# MOTOR.net
KiCad netlist of a schematic drawn in Altium Designer
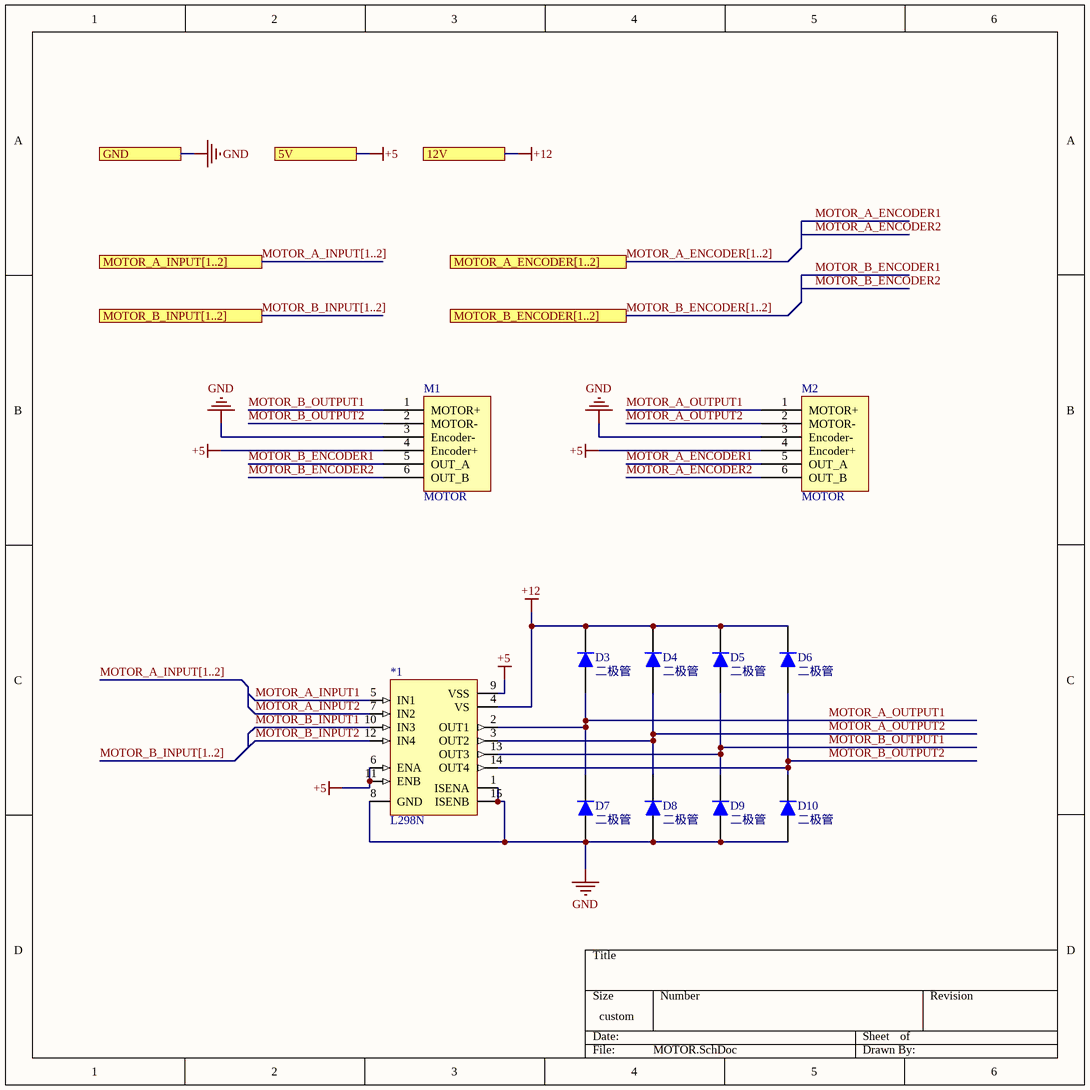
[diagram p0: MOTOR.SchDoc]

(export (version "E")
  (design (tool "Eeschema 10.0.6"))
  (components
    (comp (ref "*1") (value "L298N") (footprint "L298N-DIP") (libsource (lib "Schlib1") (part "L298N")))
    (comp (ref "D3") (value "二极管") (footprint "SOD-323") (libsource (lib "Schlib1") (part "二极管 SOD323")))
    (comp (ref "D4") (value "二极管") (footprint "SOD-323") (libsource (lib "Schlib1") (part "二极管 SOD323")))
    (comp (ref "D5") (value "二极管") (footprint "SOD-323") (libsource (lib "Schlib1") (part "二极管 SOD323")))
    (comp (ref "D6") (value "二极管") (footprint "SOD-323") (libsource (lib "Schlib1") (part "二极管 SOD323")))
    (comp (ref "D7") (value "二极管") (footprint "SOD-323") (libsource (lib "Schlib1") (part "二极管 SOD323")))
    (comp (ref "D8") (value "二极管") (footprint "SOD-323") (libsource (lib "Schlib1") (part "二极管 SOD323")))
    (comp (ref "D9") (value "二极管") (footprint "SOD-323") (libsource (lib "Schlib1") (part "二极管 SOD323")))
    (comp (ref "D10") (value "二极管") (footprint "SOD-323") (libsource (lib "Schlib1") (part "二极管 SOD323")))
    (comp (ref "M1")
      (value "MOTOR")
      (footprint "MOTOR_PORT ClearVer")
      (libsource (lib "Schlib1") (part "MOTOR_Port"))
    )
    (comp (ref "M2")
      (value "MOTOR")
      (footprint "MOTOR_PORT ClearVer")
      (libsource (lib "Schlib1") (part "MOTOR_Port"))
    )
  )
  (nets
    (net (code "1") (name "+5") (class "Default")
      (node (ref "*1") (pin "11") (pinfunction "ENB_11") (pintype "input"))
      (node (ref "*1") (pin "6") (pinfunction "ENA_6") (pintype "input"))
      (node (ref "*1") (pin "9") (pinfunction "VSS_9") (pintype "passive"))
      (node (ref "M1") (pin "4") (pinfunction "Encoder+_4") (pintype "passive"))
      (node (ref "M2") (pin "4") (pinfunction "Encoder+_4") (pintype "passive"))
    )
    (net (code "2") (name "+12") (class "Default")
      (node (ref "*1") (pin "4") (pinfunction "VS_4") (pintype "passive"))
      (node (ref "D3") (pin "1") (pinfunction "1_1") (pintype "passive"))
      (node (ref "D4") (pin "1") (pinfunction "1_1") (pintype "passive"))
      (node (ref "D5") (pin "1") (pinfunction "1_1") (pintype "passive"))
      (node (ref "D6") (pin "1") (pinfunction "1_1") (pintype "passive"))
    )
    (net (code "3") (name "/MOTOR_A_ENCODER1") (class "Default")
      (node (ref "M2") (pin "5") (pinfunction "OUT_A_5") (pintype "passive"))
    )
    (net (code "4") (name "/MOTOR_A_ENCODER2") (class "Default")
      (node (ref "M2") (pin "6") (pinfunction "OUT_B_6") (pintype "passive"))
    )
    (net (code "6") (name "/MOTOR_A_INPUT1") (class "Default")
      (node (ref "*1") (pin "5") (pinfunction "IN1_5") (pintype "input"))
    )
    (net (code "7") (name "/MOTOR_A_INPUT2") (class "Default")
      (node (ref "*1") (pin "7") (pinfunction "IN2_7") (pintype "input"))
    )
    (net (code "9") (name "/MOTOR_A_OUTPUT1") (class "Default")
      (node (ref "*1") (pin "2") (pinfunction "OUT1_2") (pintype "output"))
      (node (ref "D3") (pin "2") (pinfunction "2_2") (pintype "passive"))
      (node (ref "D7") (pin "1") (pinfunction "1_1") (pintype "passive"))
      (node (ref "M2") (pin "1") (pinfunction "MOTOR+_1") (pintype "passive"))
    )
    (net (code "10") (name "/MOTOR_A_OUTPUT2") (class "Default")
      (node (ref "*1") (pin "3") (pinfunction "OUT2_3") (pintype "output"))
      (node (ref "D4") (pin "2") (pinfunction "2_2") (pintype "passive"))
      (node (ref "D8") (pin "1") (pinfunction "1_1") (pintype "passive"))
      (node (ref "M2") (pin "2") (pinfunction "MOTOR-_2") (pintype "passive"))
    )
    (net (code "11") (name "/MOTOR_B_ENCODER1") (class "Default")
      (node (ref "M1") (pin "5") (pinfunction "OUT_A_5") (pintype "passive"))
    )
    (net (code "12") (name "/MOTOR_B_ENCODER2") (class "Default")
      (node (ref "M1") (pin "6") (pinfunction "OUT_B_6") (pintype "passive"))
    )
    (net (code "14") (name "/MOTOR_B_INPUT1") (class "Default")
      (node (ref "*1") (pin "10") (pinfunction "IN3_10") (pintype "input"))
    )
    (net (code "15") (name "/MOTOR_B_INPUT2") (class "Default")
      (node (ref "*1") (pin "12") (pinfunction "IN4_12") (pintype "input"))
    )
    (net (code "17") (name "/MOTOR_B_OUTPUT1") (class "Default")
      (node (ref "*1") (pin "13") (pinfunction "OUT3_13") (pintype "output"))
      (node (ref "D5") (pin "2") (pinfunction "2_2") (pintype "passive"))
      (node (ref "D9") (pin "1") (pinfunction "1_1") (pintype "passive"))
      (node (ref "M1") (pin "1") (pinfunction "MOTOR+_1") (pintype "passive"))
    )
    (net (code "18") (name "/MOTOR_B_OUTPUT2") (class "Default")
      (node (ref "*1") (pin "14") (pinfunction "OUT4_14") (pintype "output"))
      (node (ref "D10") (pin "1") (pinfunction "1_1") (pintype "passive"))
      (node (ref "D6") (pin "2") (pinfunction "2_2") (pintype "passive"))
      (node (ref "M1") (pin "2") (pinfunction "MOTOR-_2") (pintype "passive"))
    )
    (net (code "19") (name "GND") (class "Default")
      (node (ref "*1") (pin "1") (pinfunction "ISENA_1") (pintype "passive"))
      (node (ref "*1") (pin "15") (pinfunction "ISENB_15") (pintype "passive"))
      (node (ref "*1") (pin "8") (pinfunction "GND_8") (pintype "passive"))
      (node (ref "D10") (pin "2") (pinfunction "2_2") (pintype "passive"))
      (node (ref "D7") (pin "2") (pinfunction "2_2") (pintype "passive"))
      (node (ref "D8") (pin "2") (pinfunction "2_2") (pintype "passive"))
      (node (ref "D9") (pin "2") (pinfunction "2_2") (pintype "passive"))
      (node (ref "M1") (pin "3") (pinfunction "Encoder-_3") (pintype "passive"))
      (node (ref "M2") (pin "3") (pinfunction "Encoder-_3") (pintype "passive"))
    )
  )
)
